# LVGAmp.net
KiCad netlist of a schematic drawn in Altium Designer
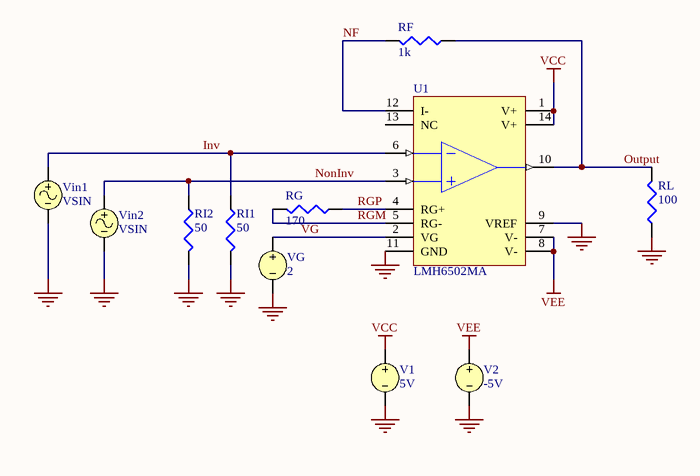
[diagram p0: LVGAmp.schdoc]

(export (version "E")
  (design (tool "Eeschema 10.0.6"))
  (components
    (comp (ref "RF")
      (value "1k")
      (description "Resistor")
      (fields (field (name "Comment") "100k"))
      (libsource (lib "") (part "RES_1"))
    )
    (comp (ref "RG")
      (value "170")
      (description "Resistor")
      (fields (field (name "Comment") "10k"))
      (libsource (lib "") (part "RES_1"))
    )
    (comp (ref "RI1")
      (value "50")
      (description "Resistor")
      (fields (field (name "Comment") "10k"))
      (libsource (lib "") (part "RES_2"))
    )
    (comp (ref "RI2")
      (value "50")
      (description "Resistor")
      (fields (field (name "Comment") "10k"))
      (libsource (lib "") (part "RES_2"))
    )
    (comp (ref "RL")
      (value "100")
      (description "Resistor")
      (fields (field (name "Comment") "25k"))
      (libsource (lib "*") (part "RES"))
    )
    (comp (ref "U1")
      (value "LMH6502MA")
      (footprint "M14A_N")
      (description "Wideband, Low Power, Linear-in-dB Variable Gain Amplifier")
      (fields
        (field (name "MANUFACTURER") "National Semiconductor")
        (field (name "DIGIKEYPARTNUMBER") "LMH6502MA-ND")
        (field (name "PUBLISHER") "Altium Limited")
      )
      (libsource (lib "NSC Amplifier with SIM models") (part "LMH6502MA"))
    )
    (comp (ref "V1")
      (value "5V")
      (description "Voltage Source")
      (fields (field (name "Comment") "12V"))
      (libsource (lib "*") (part "VSRC"))
    )
    (comp (ref "V2")
      (value "-5V")
      (description "Voltage Source")
      (fields (field (name "Comment") "-12V"))
      (libsource (lib "*") (part "VSRC"))
    )
    (comp (ref "VG")
      (value "2")
      (description "Voltage Source")
      (fields (field (name "Comment") "12V"))
      (libsource (lib "*") (part "VSRC"))
    )
    (comp (ref "Vin1")
      (value "VSIN")
      (description "Sinusoidal Voltage Source")
      (libsource (lib "*") (part "VSIN"))
    )
    (comp (ref "Vin2")
      (value "VSIN")
      (description "Sinusoidal Voltage Source")
      (libsource (lib "*") (part "VSIN"))
    )
  )
  (nets
    (net (code "1") (name "/Inv") (class "Default")
      (node (ref "RI1") (pin "2") (pinfunction "BOT_2") (pintype "passive"))
      (node (ref "U1") (pin "6") (pinfunction "VIN-_6") (pintype "input"))
      (node (ref "Vin1") (pin "1") (pinfunction "1_1") (pintype "passive"))
    )
    (net (code "2") (name "/NF") (class "Default")
      (node (ref "RF") (pin "1") (pinfunction "TOP_1") (pintype "passive"))
      (node (ref "U1") (pin "12") (pinfunction "I-_12") (pintype "passive"))
    )
    (net (code "3") (name "/NonInv") (class "Default")
      (node (ref "RI2") (pin "2") (pinfunction "BOT_2") (pintype "passive"))
      (node (ref "U1") (pin "3") (pinfunction "VIN+_3") (pintype "input"))
      (node (ref "Vin2") (pin "1") (pinfunction "1_1") (pintype "passive"))
    )
    (net (code "4") (name "/Output") (class "Default")
      (node (ref "RF") (pin "2") (pinfunction "BOT_2") (pintype "passive"))
      (node (ref "RL") (pin "1") (pinfunction "TOP_1") (pintype "passive"))
      (node (ref "U1") (pin "10") (pinfunction "VOUT_10") (pintype "output"))
    )
    (net (code "5") (name "/RGM") (class "Default")
      (node (ref "RG") (pin "1") (pinfunction "TOP_1") (pintype "passive"))
      (node (ref "U1") (pin "5") (pinfunction "RG-_5") (pintype "passive"))
    )
    (net (code "6") (name "/RGP") (class "Default")
      (node (ref "RG") (pin "2") (pinfunction "BOT_2") (pintype "passive"))
      (node (ref "U1") (pin "4") (pinfunction "RG+_4") (pintype "passive"))
    )
    (net (code "7") (name "/VG") (class "Default")
      (node (ref "U1") (pin "2") (pinfunction "VG_2") (pintype "passive"))
      (node (ref "VG") (pin "1") (pinfunction "1_1") (pintype "passive"))
    )
    (net (code "8") (name "GND") (class "Default")
      (node (ref "RI1") (pin "1") (pinfunction "TOP_1") (pintype "passive"))
      (node (ref "RI2") (pin "1") (pinfunction "TOP_1") (pintype "passive"))
      (node (ref "RL") (pin "2") (pinfunction "BOT_2") (pintype "passive"))
      (node (ref "U1") (pin "11") (pinfunction "GND_11") (pintype "power_in"))
      (node (ref "U1") (pin "9") (pinfunction "VREF_9") (pintype "passive"))
      (node (ref "V1") (pin "2") (pinfunction "2_2") (pintype "passive"))
      (node (ref "V2") (pin "2") (pinfunction "2_2") (pintype "passive"))
      (node (ref "VG") (pin "2") (pinfunction "2_2") (pintype "passive"))
      (node (ref "Vin1") (pin "2") (pinfunction "2_2") (pintype "passive"))
      (node (ref "Vin2") (pin "2") (pinfunction "2_2") (pintype "passive"))
    )
    (net (code "9") (name "VCC") (class "Default")
      (node (ref "U1") (pin "1") (pinfunction "V+_1") (pintype "power_in"))
      (node (ref "U1") (pin "14") (pinfunction "V+_14") (pintype "power_in"))
      (node (ref "V1") (pin "1") (pinfunction "1_1") (pintype "passive"))
    )
    (net (code "10") (name "VEE") (class "Default")
      (node (ref "U1") (pin "7") (pinfunction "V-_7") (pintype "power_in"))
      (node (ref "U1") (pin "8") (pinfunction "V-_8") (pintype "power_in"))
      (node (ref "V2") (pin "1") (pinfunction "1_1") (pintype "passive"))
    )
    (net (code "11") (name "unconnected-(U1-NC-Pad13)") (class "Default")
      (node (ref "U1") (pin "13") (pinfunction "NC_13") (pintype "passive"))
    )
  )
)
